# ProPrj_ProPrj_ProDoc_V12C_2026-06-01.net
KiCad netlist of a schematic drawn in EasyEDA Pro
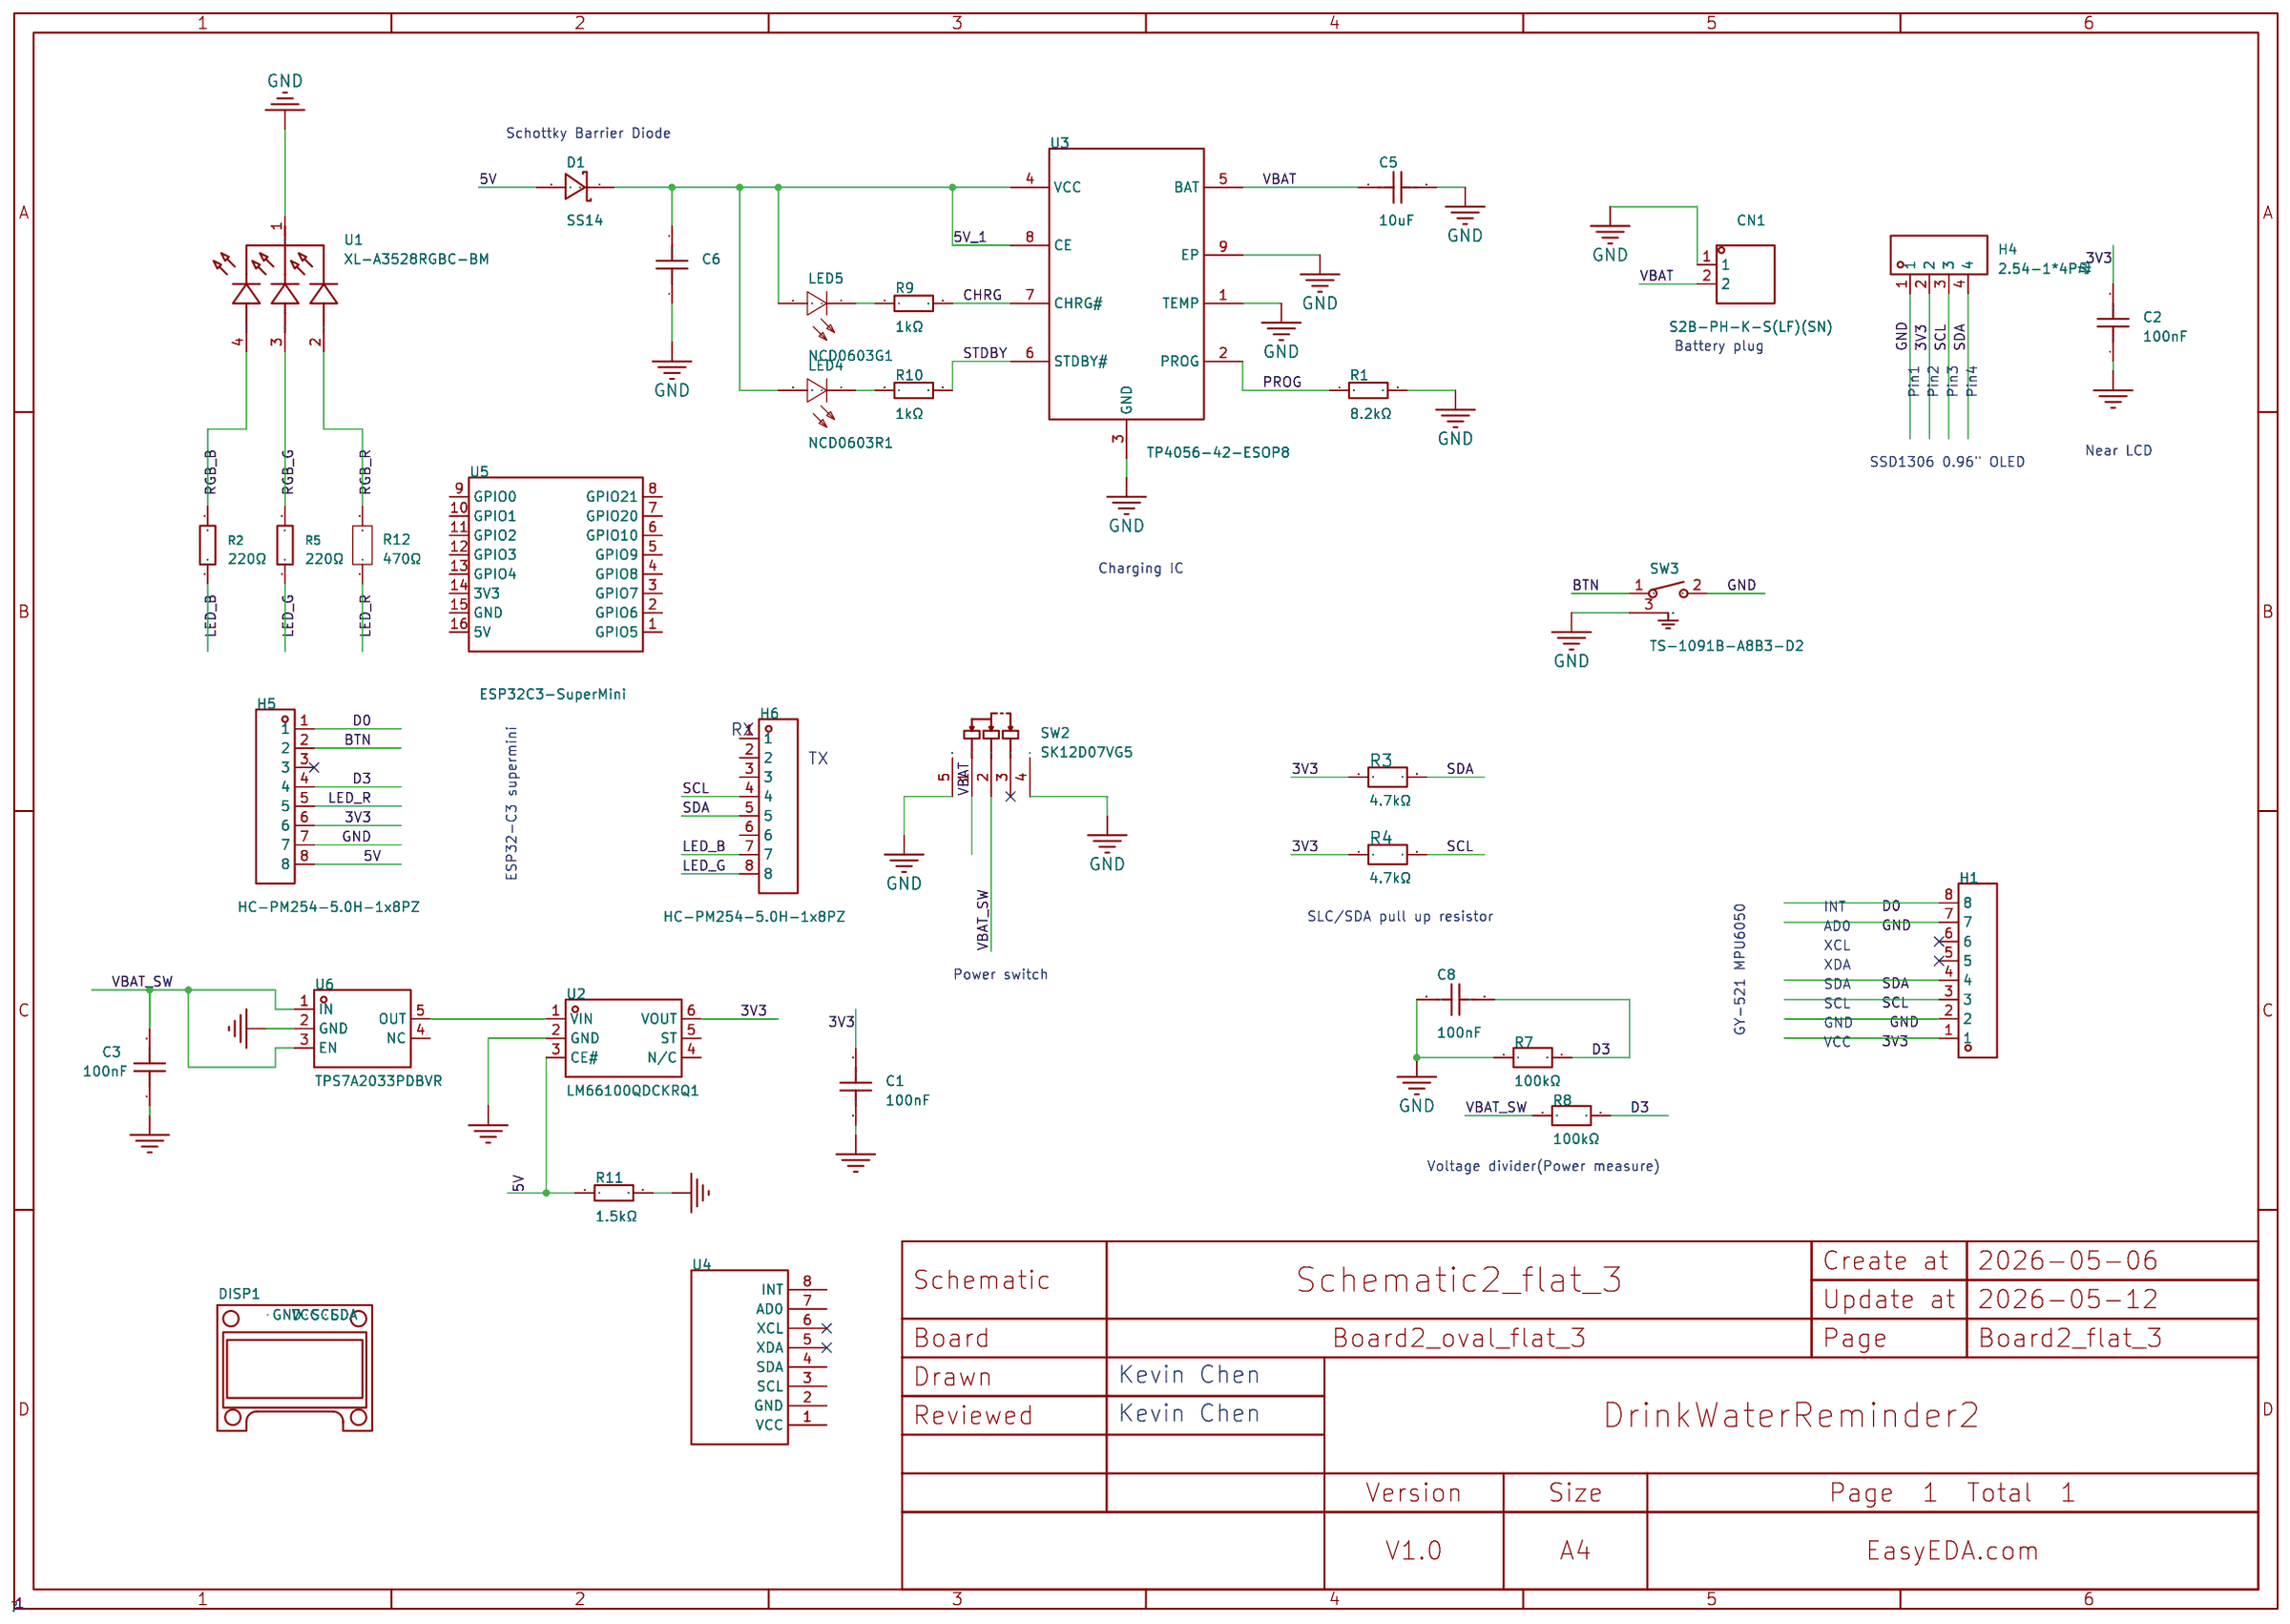
[diagram p0: schematic sheet]

(export (version "E")
  (design (tool "Eeschema 10.0.6"))
  (components
    (comp (ref "C1")
      (value "100nF")
      (footprint "easyedapro:C0603")
      (fields
        (field (name "Manufacturer Part") "GRM188R71H104KA93D")
        (field (name "Manufacturer") "muRata(村田)")
      )
      (libsource (lib "easyedapro") (part "GRM188R71H104KA93D"))
    )
    (comp (ref "C2")
      (value "100nF")
      (footprint "easyedapro:C0603")
      (fields
        (field (name "Manufacturer Part") "GRM188R71H104KA93D")
        (field (name "Manufacturer") "muRata(村田)")
      )
      (libsource (lib "easyedapro") (part "GRM188R71H104KA93D"))
    )
    (comp (ref "C3")
      (value "100nF")
      (footprint "easyedapro:C0603")
      (fields
        (field (name "Manufacturer Part") "GRM188R71H104KA93D")
        (field (name "Manufacturer") "muRata(村田)")
      )
      (libsource (lib "easyedapro") (part "GRM188R71H104KA93D"))
    )
    (comp (ref "C5")
      (value "10uF")
      (footprint "easyedapro:C0603")
      (fields
        (field (name "Manufacturer Part") "FCC0603X106K100CT")
        (field (name "Manufacturer") "FOJAN(富捷)")
      )
      (libsource (lib "easyedapro") (part "FCC0603X106K100CT"))
    )
    (comp (ref "C6")
      (value "10uF")
      (footprint "easyedapro:C0603")
      (description "Capacitance:10uF Tolerance:±10% Tolerance:±10% Voltage Rating:10V Temperature Coefficient:X5R")
      (fields
        (field (name "Manufacturer Part") "FCC0603X106K100CT")
        (field (name "Manufacturer") "FOJAN(富捷)")
      )
      (libsource (lib "easyedapro") (part "FCC0603X106K100CT"))
    )
    (comp (ref "C8")
      (value "100nF")
      (footprint "easyedapro:C0603")
      (fields
        (field (name "Manufacturer Part") "CGA0603X7R104K500JT")
        (field (name "Manufacturer") "HRE(芯声)")
      )
      (libsource (lib "easyedapro") (part "CGA0603X7R104K500JT"))
    )
    (comp (ref "CN1")
      (value "S2B-PH-K-S(LF)(SN)")
      (footprint "easyedapro:CONN-TH_S2B-PH-K-S-LF-SN")
      (fields (field (name "Manufacturer") "JST"))
      (libsource (lib "easyedapro") (part "S2B-PH-K-S(LF)(SN)"))
    )
    (comp (ref "D1")
      (value "SS14")
      (footprint "easyedapro:SMA_L4.2-W2.6-LS5.0-RD_1")
      (fields (field (name "Manufacturer") "MDD(辰达半导体)"))
      (libsource (lib "easyedapro") (part "SS14"))
    )
    (comp (ref "DISP1")
      (value "~")
      (footprint "easyedapro:SSD1306 OLED 128x64 Module")
      (libsource (lib "easyedapro") (part "SSD1306 OLED 128x64 Module"))
    )
    (comp (ref "H1")
      (value "HC-PM254-5.0H-1x8PZ")
      (footprint "easyedapro:CONN-TH_HC-PM254-1X08-8.5HZ")
      (fields (field (name "Manufacturer") "HC(虹成电子)"))
      (libsource (lib "easyedapro") (part "HC-PM254-5.0H-1X8PZ"))
    )
    (comp (ref "H4")
      (value "2.54-1*4P母")
      (footprint "easyedapro:HDR-TH_4P-P2.54-V-F")
      (fields (field (name "Manufacturer") "BOOMELE(博穆精密)"))
      (libsource (lib "easyedapro") (part "2.54-1*4P母"))
    )
    (comp (ref "H5")
      (value "HC-PM254-5.0H-1x8PZ")
      (footprint "easyedapro:CONN-TH_HC-PM254-1X08-8.5HZ")
      (fields (field (name "Manufacturer") "HC(虹成电子)"))
      (libsource (lib "easyedapro") (part "HC-PM254-5.0H-1X8PZ"))
    )
    (comp (ref "H6")
      (value "HC-PM254-5.0H-1x8PZ")
      (footprint "easyedapro:CONN-TH_HC-PM254-1X08-8.5HZ")
      (fields (field (name "Manufacturer") "HC(虹成电子)"))
      (libsource (lib "easyedapro") (part "HC-PM254-5.0H-1X8PZ"))
    )
    (comp (ref "LED4")
      (value "NCD0603R1")
      (footprint "easyedapro:LED0603-RD_1")
      (fields (field (name "Manufacturer") "国星光电"))
      (libsource (lib "easyedapro") (part "FC-D1608UGK-520D10"))
    )
    (comp (ref "LED5")
      (value "NCD0603G1")
      (footprint "easyedapro:LED0603-RD_1")
      (fields (field (name "Manufacturer") "国星光电"))
      (libsource (lib "easyedapro") (part "FC-D1608UGK-520D10"))
    )
    (comp (ref "R1")
      (value "8.2kΩ")
      (footprint "easyedapro:R0603")
      (fields (field (name "Manufacturer Part") "RC0603FR-078K2L") (field (name "Manufacturer") "YAGEO(国巨)"))
      (libsource (lib "easyedapro") (part "RC0603FR-078K2L"))
    )
    (comp (ref "R2")
      (value "220Ω")
      (footprint "easyedapro:R0603")
      (fields (field (name "Manufacturer Part") "CR0603FA2200G") (field (name "Manufacturer") "LIZ(丽智电子)"))
      (libsource (lib "easyedapro") (part "CR0603FA2200G"))
    )
    (comp (ref "R3")
      (value "4.7kΩ")
      (footprint "easyedapro:R0603")
      (fields (field (name "Manufacturer Part") "FRC0603J472 TS") (field (name "Manufacturer") "FOJAN(富捷)"))
      (libsource (lib "easyedapro") (part "FRC0603J472 TS"))
    )
    (comp (ref "R4")
      (value "4.7kΩ")
      (footprint "easyedapro:R0603")
      (fields (field (name "Manufacturer Part") "FRC0603J472 TS") (field (name "Manufacturer") "FOJAN(富捷)"))
      (libsource (lib "easyedapro") (part "FRC0603J472 TS"))
    )
    (comp (ref "R5")
      (value "220Ω")
      (footprint "easyedapro:R0603")
      (fields (field (name "Manufacturer Part") "CR0603FA2200G") (field (name "Manufacturer") "LIZ(丽智电子)"))
      (libsource (lib "easyedapro") (part "CR0603FA2200G"))
    )
    (comp (ref "R7")
      (value "100kΩ")
      (footprint "easyedapro:R0603")
      (fields (field (name "Manufacturer Part") "FRC0603J104 TS") (field (name "Manufacturer") "FOJAN(富捷)"))
      (libsource (lib "easyedapro") (part "FRC0603J104 TS"))
    )
    (comp (ref "R8")
      (value "100kΩ")
      (footprint "easyedapro:R0603")
      (fields (field (name "Manufacturer Part") "FRC0603J104 TS") (field (name "Manufacturer") "FOJAN(富捷)"))
      (libsource (lib "easyedapro") (part "FRC0603J104 TS"))
    )
    (comp (ref "R9")
      (value "1kΩ")
      (footprint "easyedapro:R0603")
      (fields
        (field (name "Manufacturer Part") "0603WAF1001T5E")
        (field (name "Manufacturer") "UNI-ROYAL(厚声)")
      )
      (libsource (lib "easyedapro") (part "0603WAF1001T5E"))
    )
    (comp (ref "R10")
      (value "1kΩ")
      (footprint "easyedapro:R0603")
      (fields
        (field (name "Manufacturer Part") "0603WAF1001T5E")
        (field (name "Manufacturer") "UNI-ROYAL(厚声)")
      )
      (libsource (lib "easyedapro") (part "0603WAF1001T5E"))
    )
    (comp (ref "R11")
      (value "1.5kΩ")
      (footprint "easyedapro:R0603")
      (fields (field (name "Manufacturer Part") "RC0603JR-071K5L") (field (name "Manufacturer") "YAGEO(国巨)"))
      (libsource (lib "easyedapro") (part "RC0603JR-071K5L"))
    )
    (comp (ref "R12")
      (value "470Ω")
      (footprint "easyedapro:R0603")
      (fields (field (name "Manufacturer Part") "FRC0603J471 TS") (field (name "Manufacturer") "FOJAN(富捷)"))
      (libsource (lib "easyedapro") (part "CR0603F470RP05Z"))
    )
    (comp (ref "SW2")
      (value "SK12D07VG5")
      (footprint "easyedapro:SW-TH_SK12D07VG5-1")
      (fields (field (name "Manufacturer") "SHOU HAN(首韩)"))
      (libsource (lib "easyedapro") (part "SK12D07VG5"))
    )
    (comp (ref "SW3")
      (value "TS-1091B-A8B3-D2")
      (footprint "easyedapro:KEY-TH_L4.5-W6.5-P3.10_TS-1091B-A8B3-D2")
      (fields (field (name "Manufacturer") "Yuandi(元迪)"))
      (libsource (lib "easyedapro") (part "TS-1091B-A8B3-D2"))
    )
    (comp (ref "U1")
      (value "XL-A3528RGBC-BM")
      (footprint "easyedapro:LED-ARRAY-SMD_4P-L3.2-W2.8-LS3.5-BL_XL-A3528RGBC-BM")
      (fields (field (name "Manufacturer") "XINGLIGHT(成兴光)"))
      (libsource (lib "easyedapro") (part "XL-A3528RGBC-BM"))
    )
    (comp (ref "U2")
      (value "LM66100QDCKRQ1")
      (footprint "easyedapro:SC-70-6_L2.0-W1.3-P0.65-LS2.1-BR")
      (fields (field (name "Manufacturer") "TI(德州仪器)"))
      (libsource (lib "easyedapro") (part "LM66100QDCKRQ1"))
    )
    (comp (ref "U3")
      (value "TP4056-42-ESOP8")
      (footprint "easyedapro:ESOP-8_L4.9-W3.9-P1.27-LS6.0-BL-EP")
      (fields (field (name "Manufacturer") "TOPPOWER(南京拓微)"))
      (libsource (lib "easyedapro") (part "TP4056"))
    )
    (comp (ref "U4")
      (value "~")
      (footprint "easyedapro:MPU-6050 module")
      (libsource (lib "easyedapro") (part "MPU-6050 module"))
    )
    (comp (ref "U5")
      (value "ESP32C3-SuperMini")
      (footprint "easyedapro:COMM-SMD_16P-L22.5-W18.0-P2.54-TL")
      (libsource (lib "easyedapro") (part "ESP32C3-SuperMini"))
    )
    (comp (ref "U6")
      (value "TPS7A2033PDBVR")
      (footprint "easyedapro:SOT-23-5_L2.9-W1.6-P0.95-LS2.8-BR")
      (fields (field (name "Manufacturer") "TI(德州仪器)"))
      (libsource (lib "easyedapro") (part "TPS7A2033PDBVR"))
    )
  )
  (nets
    (net (code "1") (name "/3V3") (class "Default")
      (node (ref "C1") (pin "2") (pinfunction "2_2") (pintype "unspecified"))
      (node (ref "C2") (pin "2") (pinfunction "2_2") (pintype "unspecified"))
      (node (ref "H1") (pin "1") (pinfunction "1_1") (pintype "unspecified"))
      (node (ref "H4") (pin "2") (pinfunction "2_2") (pintype "unspecified"))
      (node (ref "H5") (pin "6") (pinfunction "6_6") (pintype "unspecified"))
      (node (ref "R3") (pin "1") (pinfunction "1_1") (pintype "input"))
      (node (ref "R4") (pin "1") (pinfunction "1_1") (pintype "input"))
      (node (ref "U2") (pin "6") (pinfunction "VOUT_6") (pintype "unspecified"))
    )
    (net (code "2") (name "/5V") (class "Default")
      (node (ref "D1") (pin "2") (pinfunction "A_2") (pintype "unspecified"))
      (node (ref "H5") (pin "8") (pinfunction "8_8") (pintype "unspecified"))
      (node (ref "R11") (pin "1") (pinfunction "1_1") (pintype "input"))
      (node (ref "U2") (pin "3") (pinfunction "CE#_3") (pintype "unspecified"))
    )
    (net (code "3") (name "/5V_1") (class "Default")
      (node (ref "C6") (pin "2") (pinfunction "2_2") (pintype "unspecified"))
      (node (ref "D1") (pin "1") (pinfunction "K_1") (pintype "unspecified"))
      (node (ref "LED4") (pin "2") (pinfunction "A_2") (pintype "input"))
      (node (ref "LED5") (pin "2") (pinfunction "A_2") (pintype "input"))
      (node (ref "U3") (pin "4") (pinfunction "VCC_4") (pintype "unspecified"))
      (node (ref "U3") (pin "8") (pinfunction "CE_8") (pintype "unspecified"))
    )
    (net (code "4") (name "/BTN") (class "Default")
      (node (ref "H5") (pin "2") (pinfunction "2_2") (pintype "unspecified"))
      (node (ref "SW3") (pin "1") (pinfunction "1_1") (pintype "input"))
    )
    (net (code "5") (name "/CHRG") (class "Default")
      (node (ref "R9") (pin "2") (pinfunction "2_2") (pintype "input"))
      (node (ref "U3") (pin "7") (pinfunction "CHRG#_7") (pintype "unspecified"))
    )
    (net (code "6") (name "/D0") (class "Default")
      (node (ref "H1") (pin "8") (pinfunction "8_8") (pintype "unspecified"))
      (node (ref "H5") (pin "1") (pinfunction "1_1") (pintype "unspecified"))
    )
    (net (code "7") (name "/D3") (class "Default")
      (node (ref "C8") (pin "2") (pinfunction "2_2") (pintype "unspecified"))
      (node (ref "H5") (pin "4") (pinfunction "4_4") (pintype "unspecified"))
      (node (ref "R7") (pin "2") (pinfunction "2_2") (pintype "unspecified"))
      (node (ref "R8") (pin "2") (pinfunction "2_2") (pintype "unspecified"))
    )
    (net (code "8") (name "/LED_B") (class "Default")
      (node (ref "H6") (pin "7") (pinfunction "7_7") (pintype "unspecified"))
      (node (ref "R2") (pin "1") (pinfunction "1_1") (pintype "input"))
    )
    (net (code "9") (name "/LED_G") (class "Default")
      (node (ref "H6") (pin "8") (pinfunction "8_8") (pintype "unspecified"))
      (node (ref "R5") (pin "1") (pinfunction "1_1") (pintype "input"))
    )
    (net (code "10") (name "/LED_R") (class "Default")
      (node (ref "H5") (pin "5") (pinfunction "5_5") (pintype "unspecified"))
      (node (ref "R12") (pin "1") (pinfunction "1_1") (pintype "unspecified"))
    )
    (net (code "11") (name "/PROG") (class "Default")
      (node (ref "R1") (pin "1") (pinfunction "1_1") (pintype "input"))
      (node (ref "U3") (pin "2") (pinfunction "PROG_2") (pintype "unspecified"))
    )
    (net (code "12") (name "/RGB_B") (class "Default")
      (node (ref "R2") (pin "2") (pinfunction "2_2") (pintype "input"))
      (node (ref "U1") (pin "4") (pinfunction "4_4") (pintype "unspecified"))
    )
    (net (code "13") (name "/RGB_G") (class "Default")
      (node (ref "R5") (pin "2") (pinfunction "2_2") (pintype "input"))
      (node (ref "U1") (pin "3") (pinfunction "3_3") (pintype "unspecified"))
    )
    (net (code "14") (name "/RGB_R") (class "Default")
      (node (ref "R12") (pin "2") (pinfunction "2_2") (pintype "unspecified"))
      (node (ref "U1") (pin "2") (pinfunction "2_2") (pintype "unspecified"))
    )
    (net (code "15") (name "/SCL") (class "Default")
      (node (ref "H1") (pin "3") (pinfunction "3_3") (pintype "unspecified"))
      (node (ref "H4") (pin "3") (pinfunction "3_3") (pintype "unspecified"))
      (node (ref "H6") (pin "4") (pinfunction "4_4") (pintype "unspecified"))
      (node (ref "R4") (pin "2") (pinfunction "2_2") (pintype "input"))
    )
    (net (code "16") (name "/SDA") (class "Default")
      (node (ref "H1") (pin "4") (pinfunction "4_4") (pintype "unspecified"))
      (node (ref "H4") (pin "4") (pinfunction "4_4") (pintype "unspecified"))
      (node (ref "H6") (pin "5") (pinfunction "5_5") (pintype "unspecified"))
      (node (ref "R3") (pin "2") (pinfunction "2_2") (pintype "input"))
    )
    (net (code "17") (name "/STDBY") (class "Default")
      (node (ref "R10") (pin "2") (pinfunction "2_2") (pintype "input"))
      (node (ref "U3") (pin "6") (pinfunction "STDBY#_6") (pintype "unspecified"))
    )
    (net (code "18") (name "/VBAT") (class "Default")
      (node (ref "C5") (pin "1") (pinfunction "1_1") (pintype "unspecified"))
      (node (ref "CN1") (pin "2") (pinfunction "2_2") (pintype "unspecified"))
      (node (ref "SW2") (pin "1") (pinfunction "1_1") (pintype "unspecified"))
      (node (ref "U3") (pin "5") (pinfunction "BAT_5") (pintype "unspecified"))
    )
    (net (code "19") (name "/VBAT_SW") (class "Default")
      (node (ref "C3") (pin "2") (pinfunction "2_2") (pintype "unspecified"))
      (node (ref "R8") (pin "1") (pinfunction "1_1") (pintype "unspecified"))
      (node (ref "SW2") (pin "2") (pinfunction "2_2") (pintype "unspecified"))
      (node (ref "U6") (pin "1") (pinfunction "IN_1") (pintype "unspecified"))
      (node (ref "U6") (pin "3") (pinfunction "EN_3") (pintype "unspecified"))
    )
    (net (code "20") (name "GND") (class "Default")
      (node (ref "C1") (pin "1") (pinfunction "1_1") (pintype "unspecified"))
      (node (ref "C2") (pin "1") (pinfunction "1_1") (pintype "unspecified"))
      (node (ref "C3") (pin "1") (pinfunction "1_1") (pintype "unspecified"))
      (node (ref "C5") (pin "2") (pinfunction "2_2") (pintype "unspecified"))
      (node (ref "C6") (pin "1") (pinfunction "1_1") (pintype "unspecified"))
      (node (ref "C8") (pin "1") (pinfunction "1_1") (pintype "unspecified"))
      (node (ref "CN1") (pin "1") (pinfunction "1_1") (pintype "unspecified"))
      (node (ref "H1") (pin "2") (pinfunction "2_2") (pintype "unspecified"))
      (node (ref "H1") (pin "7") (pinfunction "7_7") (pintype "unspecified"))
      (node (ref "H4") (pin "1") (pinfunction "1_1") (pintype "unspecified"))
      (node (ref "H5") (pin "7") (pinfunction "7_7") (pintype "unspecified"))
      (node (ref "R1") (pin "2") (pinfunction "2_2") (pintype "input"))
      (node (ref "R11") (pin "2") (pinfunction "2_2") (pintype "input"))
      (node (ref "R7") (pin "1") (pinfunction "1_1") (pintype "unspecified"))
      (node (ref "SW2") (pin "4") (pinfunction "4_4") (pintype "unspecified"))
      (node (ref "SW2") (pin "5") (pinfunction "5_5") (pintype "unspecified"))
      (node (ref "SW3") (pin "2") (pinfunction "2_2") (pintype "input"))
      (node (ref "SW3") (pin "3") (pinfunction "GND_3") (pintype "input"))
      (node (ref "U1") (pin "1") (pinfunction "1_1") (pintype "unspecified"))
      (node (ref "U2") (pin "2") (pinfunction "GND_2") (pintype "unspecified"))
      (node (ref "U3") (pin "1") (pinfunction "TEMP_1") (pintype "unspecified"))
      (node (ref "U3") (pin "3") (pinfunction "GND_3") (pintype "unspecified"))
      (node (ref "U3") (pin "9") (pinfunction "EP_9") (pintype "unspecified"))
      (node (ref "U6") (pin "2") (pinfunction "GND_2") (pintype "unspecified"))
    )
    (net (code "21") (name "Net-(LED4-K)") (class "Default")
      (node (ref "LED4") (pin "1") (pinfunction "K_1") (pintype "input"))
      (node (ref "R10") (pin "1") (pinfunction "1_1") (pintype "input"))
    )
    (net (code "22") (name "Net-(LED5-K)") (class "Default")
      (node (ref "LED5") (pin "1") (pinfunction "K_1") (pintype "input"))
      (node (ref "R9") (pin "1") (pinfunction "1_1") (pintype "input"))
    )
    (net (code "23") (name "Net-(U2-VIN)") (class "Default")
      (node (ref "U2") (pin "1") (pinfunction "VIN_1") (pintype "unspecified"))
      (node (ref "U6") (pin "5") (pinfunction "OUT_5") (pintype "unspecified"))
    )
    (net (code "24") (name "unconnected-(DISP1-GND-Pad1)") (class "Default")
      (node (ref "DISP1") (pin "1") (pinfunction "GND_1") (pintype "input"))
    )
    (net (code "25") (name "unconnected-(DISP1-SCL-Pad3)") (class "Default")
      (node (ref "DISP1") (pin "3") (pinfunction "SCL_3") (pintype "input"))
    )
    (net (code "26") (name "unconnected-(DISP1-SDA-Pad4)") (class "Default")
      (node (ref "DISP1") (pin "4") (pinfunction "SDA_4") (pintype "input"))
    )
    (net (code "27") (name "unconnected-(DISP1-VCC-Pad2)") (class "Default")
      (node (ref "DISP1") (pin "2") (pinfunction "VCC_2") (pintype "input"))
    )
    (net (code "28") (name "unconnected-(H1-Pad5)") (class "Default")
      (node (ref "H1") (pin "5") (pinfunction "5_5") (pintype "unspecified+no_connect"))
    )
    (net (code "29") (name "unconnected-(H1-Pad6)") (class "Default")
      (node (ref "H1") (pin "6") (pinfunction "6_6") (pintype "unspecified+no_connect"))
    )
    (net (code "30") (name "unconnected-(H5-Pad3)") (class "Default")
      (node (ref "H5") (pin "3") (pinfunction "3_3") (pintype "unspecified+no_connect"))
    )
    (net (code "31") (name "unconnected-(H6-Pad1)") (class "Default")
      (node (ref "H6") (pin "1") (pinfunction "1_1") (pintype "unspecified"))
    )
    (net (code "32") (name "unconnected-(H6-Pad2)") (class "Default")
      (node (ref "H6") (pin "2") (pinfunction "2_2") (pintype "unspecified"))
    )
    (net (code "33") (name "unconnected-(H6-Pad3)") (class "Default")
      (node (ref "H6") (pin "3") (pinfunction "3_3") (pintype "unspecified"))
    )
    (net (code "34") (name "unconnected-(H6-Pad6)") (class "Default")
      (node (ref "H6") (pin "6") (pinfunction "6_6") (pintype "unspecified"))
    )
    (net (code "35") (name "unconnected-(SW2-Pad3)") (class "Default")
      (node (ref "SW2") (pin "3") (pinfunction "3_3") (pintype "unspecified+no_connect"))
    )
    (net (code "36") (name "unconnected-(U2-N{slash}C-Pad4)") (class "Default")
      (node (ref "U2") (pin "4") (pinfunction "N/C_4") (pintype "unspecified"))
    )
    (net (code "37") (name "unconnected-(U2-ST-Pad5)") (class "Default")
      (node (ref "U2") (pin "5") (pinfunction "ST_5") (pintype "unspecified"))
    )
    (net (code "38") (name "unconnected-(U4-AD0-Pad7)") (class "Default")
      (node (ref "U4") (pin "7") (pinfunction "AD0_7") (pintype "input"))
    )
    (net (code "39") (name "unconnected-(U4-GND-Pad2)") (class "Default")
      (node (ref "U4") (pin "2") (pinfunction "GND_2") (pintype "input"))
    )
    (net (code "40") (name "unconnected-(U4-INT-Pad8)") (class "Default")
      (node (ref "U4") (pin "8") (pinfunction "INT_8") (pintype "input"))
    )
    (net (code "41") (name "unconnected-(U4-SCL-Pad3)") (class "Default")
      (node (ref "U4") (pin "3") (pinfunction "SCL_3") (pintype "input"))
    )
    (net (code "42") (name "unconnected-(U4-SDA-Pad4)") (class "Default")
      (node (ref "U4") (pin "4") (pinfunction "SDA_4") (pintype "input"))
    )
    (net (code "43") (name "unconnected-(U4-VCC-Pad1)") (class "Default")
      (node (ref "U4") (pin "1") (pinfunction "VCC_1") (pintype "input"))
    )
    (net (code "44") (name "unconnected-(U4-XCL-Pad6)") (class "Default")
      (node (ref "U4") (pin "6") (pinfunction "XCL_6") (pintype "input+no_connect"))
    )
    (net (code "45") (name "unconnected-(U4-XDA-Pad5)") (class "Default")
      (node (ref "U4") (pin "5") (pinfunction "XDA_5") (pintype "input+no_connect"))
    )
    (net (code "46") (name "unconnected-(U5-3V3-Pad14)") (class "Default")
      (node (ref "U5") (pin "14") (pinfunction "3V3_14") (pintype "unspecified"))
    )
    (net (code "47") (name "unconnected-(U5-5V-Pad16)") (class "Default")
      (node (ref "U5") (pin "16") (pinfunction "5V_16") (pintype "unspecified"))
    )
    (net (code "48") (name "unconnected-(U5-GND-Pad15)") (class "Default")
      (node (ref "U5") (pin "15") (pinfunction "GND_15") (pintype "unspecified"))
    )
    (net (code "49") (name "unconnected-(U5-GPIO0-Pad9)") (class "Default")
      (node (ref "U5") (pin "9") (pinfunction "GPIO0_9") (pintype "unspecified"))
    )
    (net (code "50") (name "unconnected-(U5-GPIO1-Pad10)") (class "Default")
      (node (ref "U5") (pin "10") (pinfunction "GPIO1_10") (pintype "unspecified"))
    )
    (net (code "51") (name "unconnected-(U5-GPIO2-Pad11)") (class "Default")
      (node (ref "U5") (pin "11") (pinfunction "GPIO2_11") (pintype "unspecified"))
    )
    (net (code "52") (name "unconnected-(U5-GPIO3-Pad12)") (class "Default")
      (node (ref "U5") (pin "12") (pinfunction "GPIO3_12") (pintype "unspecified"))
    )
    (net (code "53") (name "unconnected-(U5-GPIO4-Pad13)") (class "Default")
      (node (ref "U5") (pin "13") (pinfunction "GPIO4_13") (pintype "unspecified"))
    )
    (net (code "54") (name "unconnected-(U5-GPIO5-Pad1)") (class "Default")
      (node (ref "U5") (pin "1") (pinfunction "GPIO5_1") (pintype "unspecified"))
    )
    (net (code "55") (name "unconnected-(U5-GPIO6-Pad2)") (class "Default")
      (node (ref "U5") (pin "2") (pinfunction "GPIO6_2") (pintype "unspecified"))
    )
    (net (code "56") (name "unconnected-(U5-GPIO7-Pad3)") (class "Default")
      (node (ref "U5") (pin "3") (pinfunction "GPIO7_3") (pintype "unspecified"))
    )
    (net (code "57") (name "unconnected-(U5-GPIO8-Pad4)") (class "Default")
      (node (ref "U5") (pin "4") (pinfunction "GPIO8_4") (pintype "unspecified"))
    )
    (net (code "58") (name "unconnected-(U5-GPIO9-Pad5)") (class "Default")
      (node (ref "U5") (pin "5") (pinfunction "GPIO9_5") (pintype "unspecified"))
    )
    (net (code "59") (name "unconnected-(U5-GPIO10-Pad6)") (class "Default")
      (node (ref "U5") (pin "6") (pinfunction "GPIO10_6") (pintype "unspecified"))
    )
    (net (code "60") (name "unconnected-(U5-GPIO20-Pad7)") (class "Default")
      (node (ref "U5") (pin "7") (pinfunction "GPIO20_7") (pintype "unspecified"))
    )
    (net (code "61") (name "unconnected-(U5-GPIO21-Pad8)") (class "Default")
      (node (ref "U5") (pin "8") (pinfunction "GPIO21_8") (pintype "unspecified"))
    )
    (net (code "62") (name "unconnected-(U6-NC-Pad4)") (class "Default")
      (node (ref "U6") (pin "4") (pinfunction "NC_4") (pintype "unspecified"))
    )
  )
)
